# Booster.net
KiCad netlist of a schematic drawn in Altium Designer
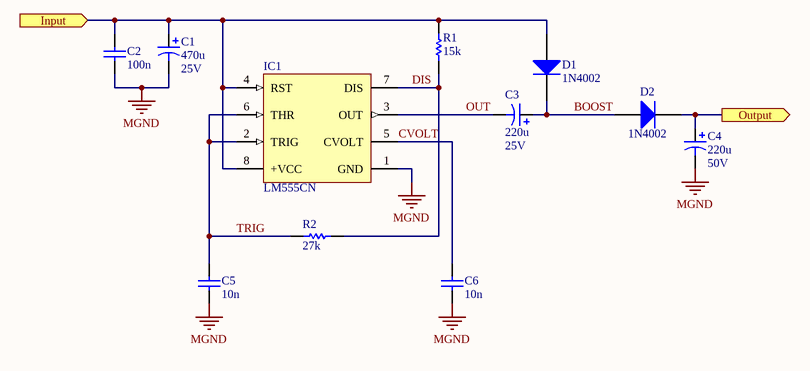
[diagram p0: Booster.SchDoc]

(export (version "E")
  (design (tool "Eeschema 10.0.6"))
  (components
    (comp (ref "C1")
      (value "470u")
      (footprint "CAP-5-ELCO-10x12.5")
      (description "Polarized Capacitor (Surface Mount)")
      (fields (field (name "VOLTAGE") "25V") (field (name "PUBLISHER") "Altium Limited"))
      (libsource (lib "Miscellaneous Devices") (part "Cap Pol3"))
    )
    (comp (ref "C2")
      (value "100n")
      (footprint "CAP-0.2-CERA")
      (description "Capacitor")
      (fields (field (name "PUBLISHER") "Altium Limited"))
      (libsource (lib "Miscellaneous Devices") (part "Cap"))
    )
    (comp (ref "C3")
      (value "220u")
      (footprint "CAP-5-ELCO-10x16")
      (description "Polarized Capacitor (Surface Mount)")
      (fields (field (name "VOLTAGE") "25V") (field (name "PUBLISHER") "Altium Limited"))
      (libsource (lib "Miscellaneous Devices") (part "Cap Pol3"))
    )
    (comp (ref "C4")
      (value "220u")
      (footprint "CAP-5-ELCO-10x16")
      (description "Polarized Capacitor (Surface Mount)")
      (fields (field (name "VOLTAGE") "50V") (field (name "PUBLISHER") "Altium Limited"))
      (libsource (lib "Miscellaneous Devices") (part "Cap Pol3"))
    )
    (comp (ref "C5")
      (value "10n")
      (footprint "CAP-0.1-CERA2")
      (description "Capacitor")
      (fields (field (name "PUBLISHER") "Altium Limited"))
      (libsource (lib "Miscellaneous Devices") (part "Cap"))
    )
    (comp (ref "C6")
      (value "10n")
      (footprint "CAP-0.1-CERA2")
      (description "Capacitor")
      (fields (field (name "PUBLISHER") "Altium Limited"))
      (libsource (lib "Miscellaneous Devices") (part "Cap"))
    )
    (comp (ref "D1")
      (value "1N4002")
      (footprint "DIODE-0.3-SI")
      (description "1 Amp General Purpose Rectifier")
      (fields (field (name "PUBLISHER") "Altium Limited"))
      (libsource (lib "Miscellaneous Devices") (part "Diode 1N4002"))
    )
    (comp (ref "D2")
      (value "1N4002")
      (footprint "DIODE-0.3-SI")
      (description "1 Amp General Purpose Rectifier")
      (fields (field (name "PUBLISHER") "Altium Limited"))
      (libsource (lib "Miscellaneous Devices") (part "Diode 1N4002"))
    )
    (comp (ref "IC1")
      (value "LM555CN")
      (footprint "IC-DIP-8")
      (description "Timer")
      (fields
        (field (name "MANUFACTURER") "National Semiconductor")
        (field (name "DIGIKEYPARTNUMBER") "LM555CNNS-ND")
        (field (name "PUBLISHER") "Altium Limited")
      )
      (libsource (lib "NSC Analog") (part "LM555CN"))
    )
    (comp (ref "R1")
      (value "15k")
      (footprint "RES-0.4")
      (description "Resistor")
      (fields (field (name "PUBLISHER") "Altium Limited"))
      (libsource (lib "Miscellaneous Devices") (part "Res1"))
    )
    (comp (ref "R2")
      (value "27k")
      (footprint "RES-0.4")
      (description "Resistor")
      (fields (field (name "PUBLISHER") "Altium Limited"))
      (libsource (lib "Miscellaneous Devices") (part "Res1"))
    )
  )
  (nets
    (net (code "1") (name "/BOOST") (class "Default")
      (node (ref "C3") (pin "1") (pinfunction "1_1") (pintype "passive"))
      (node (ref "D1") (pin "2") (pinfunction "K_2") (pintype "passive"))
      (node (ref "D2") (pin "1") (pinfunction "A_1") (pintype "passive"))
    )
    (net (code "2") (name "/CVOLT") (class "Default")
      (node (ref "C6") (pin "2") (pinfunction "2_2") (pintype "passive"))
      (node (ref "IC1") (pin "5") (pinfunction "CVOLT_5") (pintype "passive"))
    )
    (net (code "3") (name "/DIS") (class "Default")
      (node (ref "IC1") (pin "7") (pinfunction "DIS_7") (pintype "open_collector"))
      (node (ref "R1") (pin "2") (pinfunction "2_2") (pintype "passive"))
      (node (ref "R2") (pin "2") (pinfunction "2_2") (pintype "passive"))
    )
    (net (code "4") (name "/Input") (class "Default")
      (node (ref "C1") (pin "1") (pinfunction "1_1") (pintype "passive"))
      (node (ref "C2") (pin "2") (pinfunction "2_2") (pintype "passive"))
      (node (ref "D1") (pin "1") (pinfunction "A_1") (pintype "passive"))
      (node (ref "IC1") (pin "4") (pinfunction "RST_4") (pintype "input"))
      (node (ref "IC1") (pin "8") (pinfunction "+VCC_8") (pintype "power_in"))
      (node (ref "R1") (pin "1") (pinfunction "1_1") (pintype "passive"))
    )
    (net (code "5") (name "/OUT") (class "Default")
      (node (ref "C3") (pin "2") (pinfunction "2_2") (pintype "passive"))
      (node (ref "IC1") (pin "3") (pinfunction "OUT_3") (pintype "output"))
    )
    (net (code "6") (name "/Output") (class "Default")
      (node (ref "C4") (pin "1") (pinfunction "1_1") (pintype "passive"))
      (node (ref "D2") (pin "2") (pinfunction "K_2") (pintype "passive"))
    )
    (net (code "7") (name "/TRIG") (class "Default")
      (node (ref "C5") (pin "2") (pinfunction "2_2") (pintype "passive"))
      (node (ref "IC1") (pin "2") (pinfunction "TRIG_2") (pintype "input"))
      (node (ref "IC1") (pin "6") (pinfunction "THR_6") (pintype "input"))
      (node (ref "R2") (pin "1") (pinfunction "1_1") (pintype "passive"))
    )
    (net (code "8") (name "MGND") (class "Default")
      (node (ref "C1") (pin "2") (pinfunction "2_2") (pintype "passive"))
      (node (ref "C2") (pin "1") (pinfunction "1_1") (pintype "passive"))
      (node (ref "C4") (pin "2") (pinfunction "2_2") (pintype "passive"))
      (node (ref "C5") (pin "1") (pinfunction "1_1") (pintype "passive"))
      (node (ref "C6") (pin "1") (pinfunction "1_1") (pintype "passive"))
      (node (ref "IC1") (pin "1") (pinfunction "GND_1") (pintype "power_in"))
    )
  )
)
